# Current_sence-load-volt_meter.net
KiCad netlist of a schematic drawn in Altium Designer
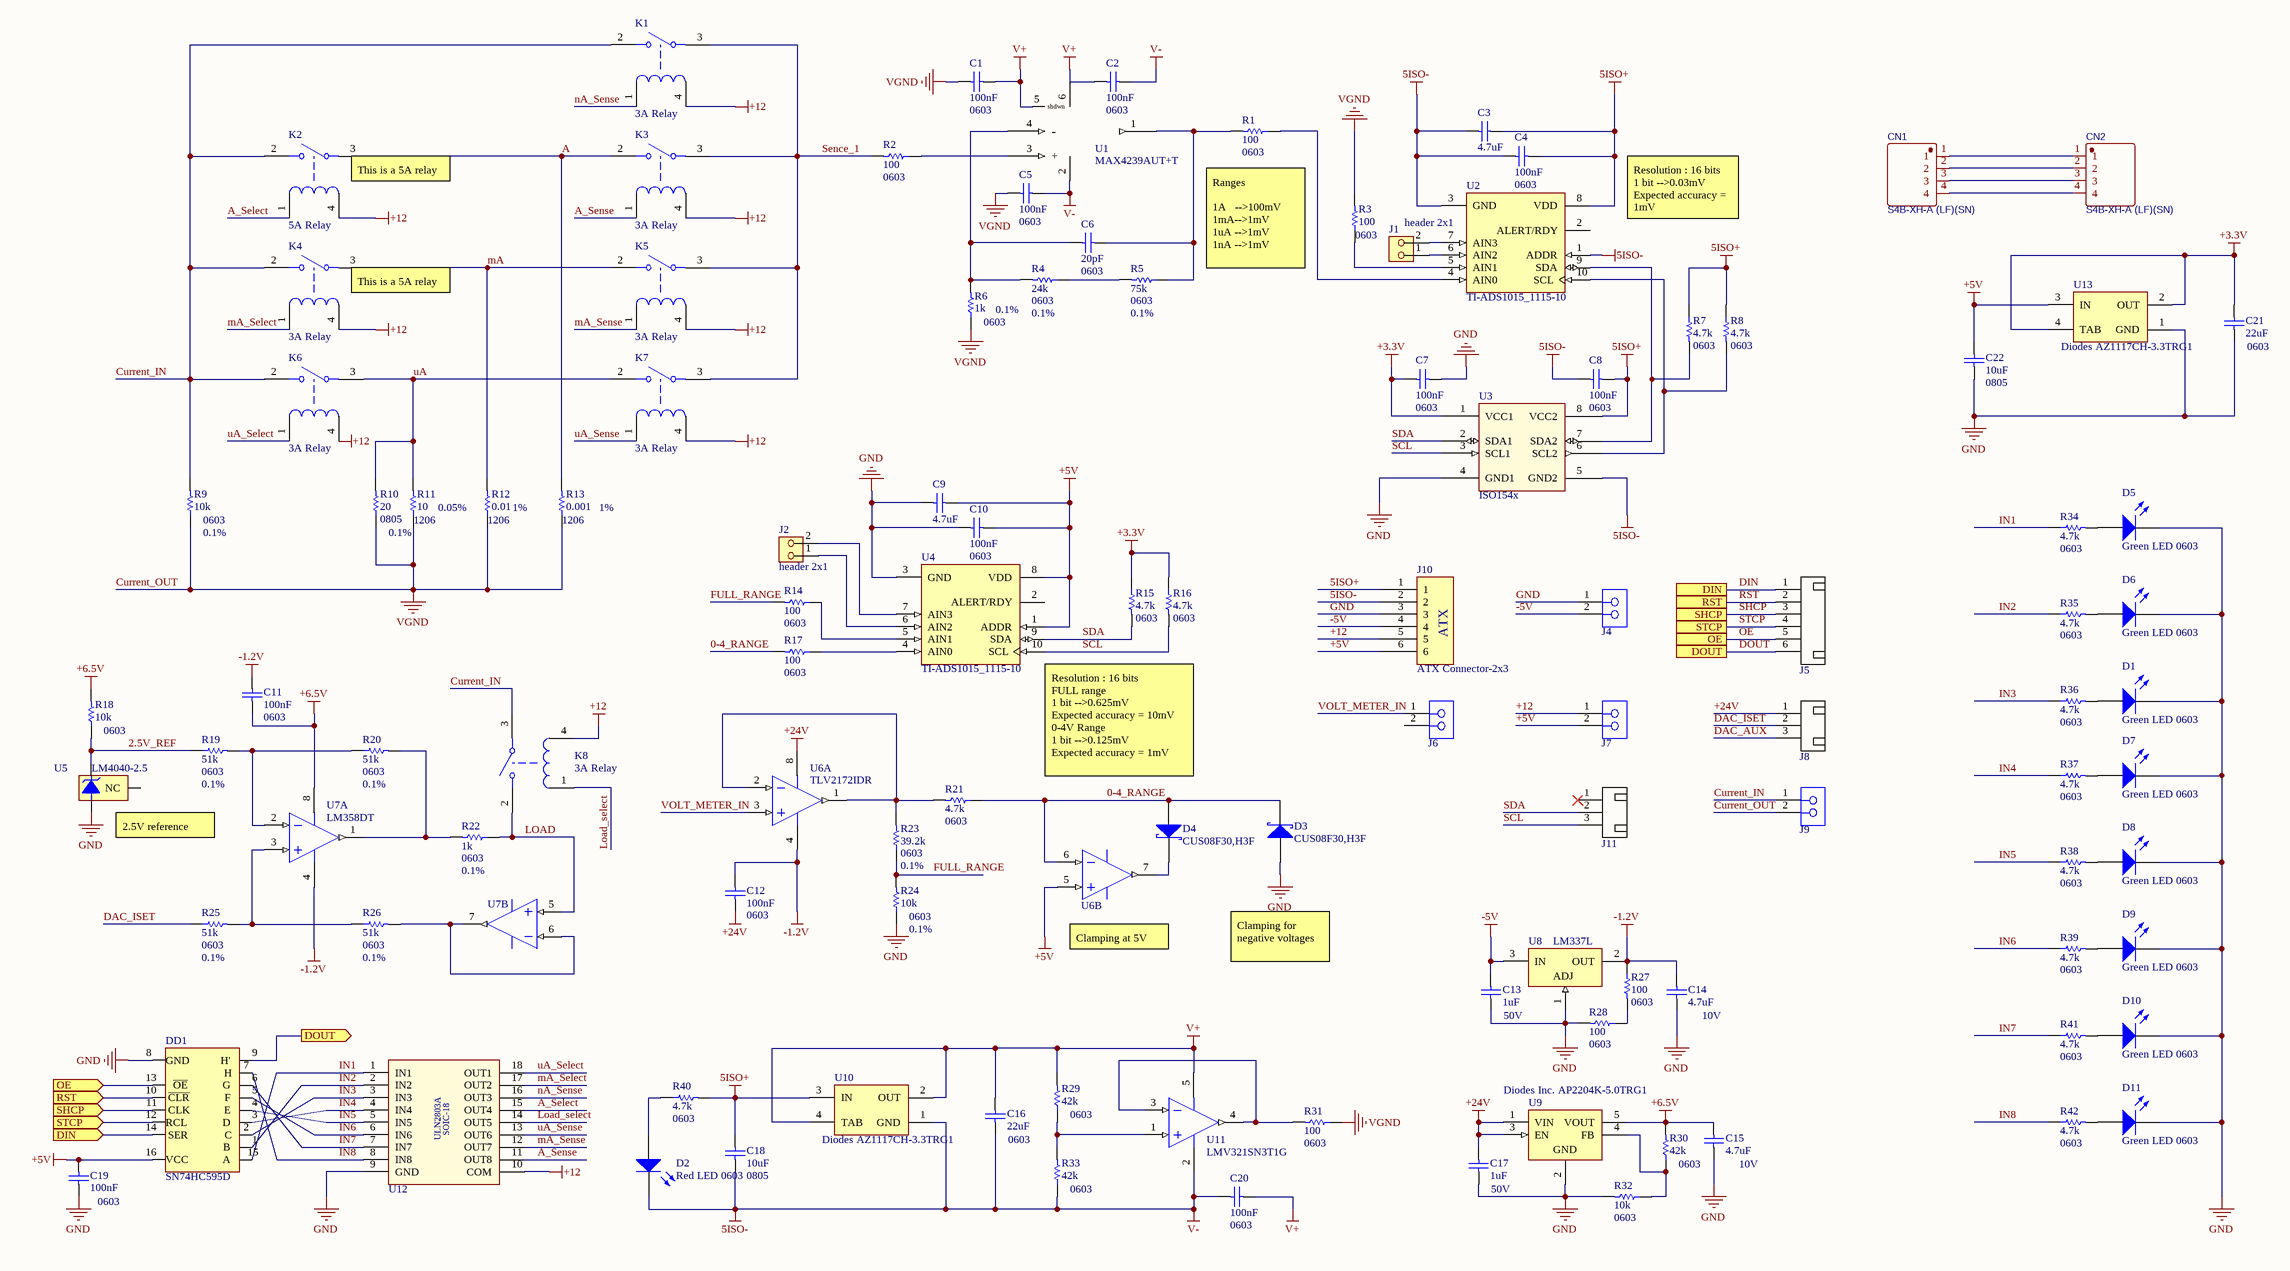
[diagram p0: Current_sence-load-volt_meter.SchDoc]

(export (version "E")
  (design (tool "Eeschema 10.0.6"))
  (components
    (comp (ref "C1")
      (value "100nF")
      (footprint "CAPC1608X09N")
      (description "0603 10 nF 50 V ± 10% Tolerance X7R Surface Mount Multilayer Ceramic Capacitor")
      (fields
        (field (name "MANUFACTURE PART NUMBER") "CC0603KRX7R9BB104")
        (field (name "MANUFACTURER") "YAGEO")
        (field (name "PACKAGE / CASE") "0603")
      )
      (libsource (lib "Current_sence_unit") (part "CMP-2f55e5122ad9f092-5"))
    )
    (comp (ref "C2")
      (value "100nF")
      (footprint "CAPC1608X09N")
      (description "0603 10 nF 50 V ± 10% Tolerance X7R Surface Mount Multilayer Ceramic Capacitor")
      (fields
        (field (name "MANUFACTURE PART NUMBER") "CC0603KRX7R9BB104")
        (field (name "MANUFACTURER") "YAGEO")
        (field (name "PACKAGE / CASE") "0603")
      )
      (libsource (lib "Current_sence_unit") (part "CMP-2f55e5122ad9f092-5"))
    )
    (comp (ref "C3")
      (value "4.7uF")
      (footprint "CAPC1608X09N")
      (description "0603 10 nF 50 V ± 10% Tolerance X7R Surface Mount Multilayer Ceramic Capacitor")
      (fields
        (field (name "MANUFACTURE PART NUMBER") "CL10A475KP8NNNC")
        (field (name "MANUFACTURER") "Samsung Electro-Mechanics")
      )
      (libsource (lib "Current_sence_unit") (part "CMP-2f55e5122ad9f092-5"))
    )
    (comp (ref "C4")
      (value "100nF")
      (footprint "CAPC1608X09N")
      (description "0603 10 nF 50 V ± 10% Tolerance X7R Surface Mount Multilayer Ceramic Capacitor")
      (fields
        (field (name "MANUFACTURE PART NUMBER") "CC0603KRX7R9BB104")
        (field (name "MANUFACTURER") "YAGEO")
        (field (name "PACKAGE / CASE") "0603")
      )
      (libsource (lib "Current_sence_unit") (part "CMP-2f55e5122ad9f092-5"))
    )
    (comp (ref "C5")
      (value "100nF")
      (footprint "CAPC1608X09N")
      (description "0603 10 nF 50 V ± 10% Tolerance X7R Surface Mount Multilayer Ceramic Capacitor")
      (fields
        (field (name "MANUFACTURE PART NUMBER") "CC0603KRX7R9BB104")
        (field (name "MANUFACTURER") "YAGEO")
        (field (name "PACKAGE / CASE") "0603")
      )
      (libsource (lib "Current_sence_unit") (part "CMP-2f55e5122ad9f092-5"))
    )
    (comp (ref "C6")
      (value "20pF")
      (footprint "CAPC1608X09N")
      (description "0603 10 nF 50 V ± 10% Tolerance X7R Surface Mount Multilayer Ceramic Capacitor")
      (fields
        (field (name "MANUFACTURE PART NUMBER") "CC0603JRNPO9BN200")
        (field (name "MANUFACTURER") "YAGEO")
        (field (name "PACKAGE / CASE") "0603")
      )
      (libsource (lib "Current_sence_unit") (part "CMP-2f55e5122ad9f092-5"))
    )
    (comp (ref "C7")
      (value "100nF")
      (footprint "CAPC1608X09N")
      (description "0603 10 nF 50 V ± 10% Tolerance X7R Surface Mount Multilayer Ceramic Capacitor")
      (fields
        (field (name "MANUFACTURE PART NUMBER") "CC0603KRX7R9BB104")
        (field (name "MANUFACTURER") "YAGEO")
        (field (name "PACKAGE / CASE") "0603")
      )
      (libsource (lib "Current_sence_unit") (part "CMP-2f55e5122ad9f092-5"))
    )
    (comp (ref "C8")
      (value "100nF")
      (footprint "CAPC1608X09N")
      (description "0603 10 nF 50 V ± 10% Tolerance X7R Surface Mount Multilayer Ceramic Capacitor")
      (fields
        (field (name "MANUFACTURE PART NUMBER") "CC0603KRX7R9BB104")
        (field (name "MANUFACTURER") "YAGEO")
        (field (name "PACKAGE / CASE") "0603")
      )
      (libsource (lib "Current_sence_unit") (part "CMP-2f55e5122ad9f092-5"))
    )
    (comp (ref "C9")
      (value "4.7uF")
      (footprint "CAPC1608X09N")
      (description "0603 10 nF 50 V ± 10% Tolerance X7R Surface Mount Multilayer Ceramic Capacitor")
      (fields
        (field (name "MANUFACTURE PART NUMBER") "CL10A475KP8NNNC")
        (field (name "MANUFACTURER") "Samsung Electro-Mechanics")
      )
      (libsource (lib "Current_sence_unit") (part "CMP-2f55e5122ad9f092-5"))
    )
    (comp (ref "C10")
      (value "100nF")
      (footprint "CAPC1608X09N")
      (description "0603 10 nF 50 V ± 10% Tolerance X7R Surface Mount Multilayer Ceramic Capacitor")
      (fields
        (field (name "MANUFACTURE PART NUMBER") "CC0603KRX7R9BB104")
        (field (name "MANUFACTURER") "YAGEO")
        (field (name "PACKAGE / CASE") "0603")
      )
      (libsource (lib "Current_sence_unit") (part "CMP-2f55e5122ad9f092-5"))
    )
    (comp (ref "C11")
      (value "100nF")
      (footprint "CAPC1608X09N")
      (description "0603 10 nF 50 V ± 10% Tolerance X7R Surface Mount Multilayer Ceramic Capacitor")
      (fields
        (field (name "MANUFACTURE PART NUMBER") "CC0603KRX7R9BB104")
        (field (name "MANUFACTURER") "YAGEO")
        (field (name "PACKAGE / CASE") "0603")
      )
      (libsource (lib "Current_sence_unit") (part "CMP-2f55e5122ad9f092-5"))
    )
    (comp (ref "C12")
      (value "100nF")
      (footprint "CAPC1608X09N")
      (description "0603 10 nF 50 V ± 10% Tolerance X7R Surface Mount Multilayer Ceramic Capacitor")
      (fields
        (field (name "MANUFACTURE PART NUMBER") "CC0603KRX7R9BB104")
        (field (name "MANUFACTURER") "YAGEO")
        (field (name "PACKAGE / CASE") "0603")
      )
      (libsource (lib "Current_sence_unit") (part "CMP-2f55e5122ad9f092-5"))
    )
    (comp (ref "C13")
      (value "1uF")
      (footprint "CAPC1608X09N")
      (description "0603 10 nF 50 V ± 10% Tolerance X7R Surface Mount Multilayer Ceramic Capacitor")
      (fields
        (field (name "VOLTAGE-RATED") "50V")
        (field (name "MANUFACTURE PART NUMBER") "CL21B105KBFNNNE")
        (field (name "MANUFACTURER") "Samsung Electro-Mechanics")
      )
      (libsource (lib "Current_sence_unit") (part "CMP-2f55e5122ad9f092-5"))
    )
    (comp (ref "C14")
      (value "4.7uF")
      (footprint "CAPC1608X09N")
      (description "0603 10 nF 50 V ± 10% Tolerance X7R Surface Mount Multilayer Ceramic Capacitor")
      (fields
        (field (name "VOLTAGE-RATED") "10V")
        (field (name "MANUFACTURE PART NUMBER") "CL10A475KP8NNNC")
        (field (name "MANUFACTURER") "Samsung Electro-Mechanics")
      )
      (libsource (lib "Current_sence_unit") (part "CMP-2f55e5122ad9f092-5"))
    )
    (comp (ref "C15")
      (value "4.7uF")
      (footprint "CAPC1608X09N")
      (description "0603 10 nF 50 V ± 10% Tolerance X7R Surface Mount Multilayer Ceramic Capacitor")
      (fields
        (field (name "VOLTAGE-RATED") "10V")
        (field (name "MANUFACTURE PART NUMBER") "CL10A475KP8NNNC")
        (field (name "MANUFACTURER") "Samsung Electro-Mechanics")
      )
      (libsource (lib "Current_sence_unit") (part "CMP-2f55e5122ad9f092-5"))
    )
    (comp (ref "C16")
      (value "22uF")
      (footprint "CAPC1608X09N")
      (description "0603 10 nF 50 V ± 10% Tolerance X7R Surface Mount Multilayer Ceramic Capacitor")
      (fields
        (field (name "MANUFACTURE PART NUMBER") "CL10A226MP8NUNE")
        (field (name "MANUFACTURER") "Samsung Electro-Mechanics")
        (field (name "PACKAGE / CASE") "0603")
      )
      (libsource (lib "Current_sence_unit") (part "CMP-2f55e5122ad9f092-5"))
    )
    (comp (ref "C17")
      (value "1uF")
      (footprint "CAPC1608X09N")
      (description "0603 10 nF 50 V ± 10% Tolerance X7R Surface Mount Multilayer Ceramic Capacitor")
      (fields
        (field (name "VOLTAGE-RATED") "50V")
        (field (name "MANUFACTURE PART NUMBER") "CL21B105KBFNNNE")
        (field (name "MANUFACTURER") "Samsung Electro-Mechanics")
      )
      (libsource (lib "Current_sence_unit") (part "CMP-2f55e5122ad9f092-5"))
    )
    (comp (ref "C18")
      (value "10uF")
      (footprint "C0805")
      (description "Cap Ceramic 0.1uF 50V X7R 10% SMD 0805 125C Embossed T/R")
      (fields
        (field (name "MANUFACTURE PART NUMBER") "CL21B106KOQNNNE")
        (field (name "PACKAGE / CASE") "0805")
        (field (name "MANUFACTURER") "Samsung Electro-Mechanics")
      )
      (libsource (lib "Current_sence_unit") (part "CMP-135114-3"))
    )
    (comp (ref "C19")
      (value "100nF")
      (footprint "CAPC1608X09N")
      (description "0603 10 nF 50 V ± 10% Tolerance X7R Surface Mount Multilayer Ceramic Capacitor")
      (fields
        (field (name "MANUFACTURE PART NUMBER") "CC0603KRX7R9BB104")
        (field (name "MANUFACTURER") "YAGEO")
        (field (name "PACKAGE / CASE") "0603")
      )
      (libsource (lib "Current_sence_unit") (part "CMP-2f55e5122ad9f092-5"))
    )
    (comp (ref "C20")
      (value "100nF")
      (footprint "CAPC1608X09N")
      (description "0603 10 nF 50 V ± 10% Tolerance X7R Surface Mount Multilayer Ceramic Capacitor")
      (fields
        (field (name "MANUFACTURE PART NUMBER") "CC0603KRX7R9BB104")
        (field (name "MANUFACTURER") "YAGEO")
        (field (name "PACKAGE / CASE") "0603")
      )
      (libsource (lib "Current_sence_unit") (part "CMP-2f55e5122ad9f092-5"))
    )
    (comp (ref "C21")
      (value "22uF")
      (footprint "CAPC1608X09N")
      (description "0603 10 nF 50 V ± 10% Tolerance X7R Surface Mount Multilayer Ceramic Capacitor")
      (fields
        (field (name "MANUFACTURE PART NUMBER") "CL10A226MP8NUNE")
        (field (name "MANUFACTURER") "Samsung Electro-Mechanics")
        (field (name "PACKAGE / CASE") "0603")
      )
      (libsource (lib "Current_sence_unit") (part "CMP-2f55e5122ad9f092-5"))
    )
    (comp (ref "C22")
      (value "10uF")
      (footprint "C0805")
      (description "Cap Ceramic 0.1uF 50V X7R 10% SMD 0805 125C Embossed T/R")
      (fields
        (field (name "MANUFACTURE PART NUMBER") "CL21B106KOQNNNE")
        (field (name "PACKAGE / CASE") "0805")
        (field (name "MANUFACTURER") "Samsung Electro-Mechanics")
      )
      (libsource (lib "Current_sence_unit") (part "CMP-135114-3"))
    )
    (comp (ref "CN1")
      (value "S4B-XH-A (LF)(SN)")
      (footprint "CONN-TH_S4B-XH-A (LF)(SN)")
      (fields (field (name "MANUFACTURER") "JST Sales America") (field (name "CONTRIBUTOR") "LCSC"))
      (libsource (lib "Main_MCU") (part "S4B-XH-A (LF)(SN)"))
    )
    (comp (ref "CN2")
      (value "S4B-XH-A (LF)(SN)")
      (footprint "CONN-TH_S4B-XH-A (LF)(SN)")
      (fields (field (name "MANUFACTURER") "JST Sales America") (field (name "CONTRIBUTOR") "LCSC"))
      (libsource (lib "Main_MCU") (part "S4B-XH-A (LF)(SN)"))
    )
    (comp (ref "D1")
      (value "Green LED 0603")
      (footprint "0603LED_GEN")
      (description "Generic LED 0603")
      (fields (field (name "MANUFACTURER") "Orient") (field (name "MANUFACTURE PART NUMBER") "ORH-G36G"))
      (libsource (lib "Current_sence_unit") (part "CMP-7ejgl1mi36gtz3spabtw-1"))
    )
    (comp (ref "D2")
      (value "Red LED 0603")
      (footprint "0603LED_GEN")
      (description "Generic LED 0603")
      (fields
        (field (name "MANUFACTURER") "Everlight Elec")
        (field (name "MANUFACTURE PART NUMBER") "19-217/R6C-AL1M2VY/3T")
      )
      (libsource (lib "Current_sence_unit") (part "CMP-7ejgl1mi36gtz3spabtw-1"))
    )
    (comp (ref "D3")
      (value "CUS08F30,H3F")
      (footprint "PCB-7qpkjsjx5cjbarp1o0hc-1")
      (description "Diode Schottky 30V 2-Pin SOD-323")
      (fields (field (name "MANUFACTURER") "TOSHIBA"))
      (libsource (lib "Current_sence_unit") (part "CMP-df191521a52000de-2"))
    )
    (comp (ref "D4")
      (value "CUS08F30,H3F")
      (footprint "PCB-7qpkjsjx5cjbarp1o0hc-1")
      (description "Diode Schottky 30V 2-Pin SOD-323")
      (fields (field (name "MANUFACTURER") "TOSHIBA"))
      (libsource (lib "Current_sence_unit") (part "CMP-df191521a52000de-2"))
    )
    (comp (ref "D5")
      (value "Green LED 0603")
      (footprint "0603LED_GEN")
      (description "Generic LED 0603")
      (fields (field (name "MANUFACTURER") "Orient") (field (name "MANUFACTURE PART NUMBER") "ORH-G36G"))
      (libsource (lib "Current_sence_unit") (part "CMP-7ejgl1mi36gtz3spabtw-1"))
    )
    (comp (ref "D6")
      (value "Green LED 0603")
      (footprint "0603LED_GEN")
      (description "Generic LED 0603")
      (fields (field (name "MANUFACTURER") "Orient") (field (name "MANUFACTURE PART NUMBER") "ORH-G36G"))
      (libsource (lib "Current_sence_unit") (part "CMP-7ejgl1mi36gtz3spabtw-1"))
    )
    (comp (ref "D7")
      (value "Green LED 0603")
      (footprint "0603LED_GEN")
      (description "Generic LED 0603")
      (fields (field (name "MANUFACTURER") "Orient") (field (name "MANUFACTURE PART NUMBER") "ORH-G36G"))
      (libsource (lib "Current_sence_unit") (part "CMP-7ejgl1mi36gtz3spabtw-1"))
    )
    (comp (ref "D8")
      (value "Green LED 0603")
      (footprint "0603LED_GEN")
      (description "Generic LED 0603")
      (fields (field (name "MANUFACTURER") "Orient") (field (name "MANUFACTURE PART NUMBER") "ORH-G36G"))
      (libsource (lib "Current_sence_unit") (part "CMP-7ejgl1mi36gtz3spabtw-1"))
    )
    (comp (ref "D9")
      (value "Green LED 0603")
      (footprint "0603LED_GEN")
      (description "Generic LED 0603")
      (fields (field (name "MANUFACTURER") "Orient") (field (name "MANUFACTURE PART NUMBER") "ORH-G36G"))
      (libsource (lib "Current_sence_unit") (part "CMP-7ejgl1mi36gtz3spabtw-1"))
    )
    (comp (ref "D10")
      (value "Green LED 0603")
      (footprint "0603LED_GEN")
      (description "Generic LED 0603")
      (fields (field (name "MANUFACTURER") "Orient") (field (name "MANUFACTURE PART NUMBER") "ORH-G36G"))
      (libsource (lib "Current_sence_unit") (part "CMP-7ejgl1mi36gtz3spabtw-1"))
    )
    (comp (ref "D11")
      (value "Green LED 0603")
      (footprint "0603LED_GEN")
      (description "Generic LED 0603")
      (fields (field (name "MANUFACTURER") "Orient") (field (name "MANUFACTURE PART NUMBER") "ORH-G36G"))
      (libsource (lib "Current_sence_unit") (part "CMP-7ejgl1mi36gtz3spabtw-1"))
    )
    (comp (ref "DD1")
      (value "SN74HC595D")
      (footprint "PCB-72k1vk0k27b6qyyenbg0-1")
      (description "Shift Register Single 8-Bit Serial to Serial/Parallel 16-Pin SOIC Tube")
      (fields
        (field (name "MANUFACTURE PART NUMBER") "74HC595D,118")
        (field (name "MANUFACTURER") "Nexperia")
      )
      (libsource (lib "Current_sence_unit") (part "CMP-ded317d957220114-5"))
    )
    (comp (ref "J1")
      (value "header 2x1")
      (footprint "PCB-55llon6gpk2h6a06nz0l-1")
      (description "2.54mm (.100\") Pitch C-Grid III Header, Single Row, Vertical, 1 Circuits, Gold (Au) Plating")
      (libsource (lib "Current_sence_unit") (part "SYM-8fae46aeaafe5069-1"))
    )
    (comp (ref "J2")
      (value "header 2x1")
      (footprint "PCB-55llon6gpk2h6a06nz0l-1")
      (description "2.54mm (.100\") Pitch C-Grid III Header, Single Row, Vertical, 1 Circuits, Gold (Au) Plating")
      (libsource (lib "Current_sence_unit") (part "SYM-8fae46aeaafe5069-1"))
    )
    (comp (ref "J4")
      (value "DB126V-5.0-2P-GN")
      (footprint "PCB-kiok1jlp9o9fcwf1wwvf-1")
      (description "Block, Terminal; 13.5 A; 250 V; 5 mm; 26 to 16 AWG; 2; Screw; Solder; 4 kV; PA")
      (fields (field (name "MANUFACTURER") "DIBO"))
      (libsource (lib "Current_sence_unit") (part "CMP-7ad9b3d37ed8a51e-5"))
    )
    (comp (ref "J5")
      (value "JST S6B-XH-A")
      (footprint "JST S6B-XH-A")
      (description "Socket; wire-board; male; PIN: 6; 2.5mm; THT; XH; 250V; 3A; -25÷85°C")
      (fields
        (field (name "MANUFACTURER") "JST Sales America")
        (field (name "MANUFACTURE PART NUMBER") "S6B-XH-A(LF)(SN)")
      )
      (libsource (lib "Current_sence_unit") (part "CMP-239aeae271c2fc5d-12"))
    )
    (comp (ref "J6")
      (value "DB126V-5.0-2P-GN")
      (footprint "PCB-kiok1jlp9o9fcwf1wwvf-1")
      (description "Block, Terminal; 13.5 A; 250 V; 5 mm; 26 to 16 AWG; 2; Screw; Solder; 4 kV; PA")
      (fields (field (name "MANUFACTURER") "DIBO"))
      (libsource (lib "Current_sence_unit") (part "CMP-7ad9b3d37ed8a51e-5"))
    )
    (comp (ref "J7")
      (value "DB126V-5.0-2P-GN")
      (footprint "PCB-kiok1jlp9o9fcwf1wwvf-1")
      (description "Block, Terminal; 13.5 A; 250 V; 5 mm; 26 to 16 AWG; 2; Screw; Solder; 4 kV; PA")
      (fields (field (name "MANUFACTURER") "DIBO"))
      (libsource (lib "Current_sence_unit") (part "CMP-7ad9b3d37ed8a51e-5"))
    )
    (comp (ref "J8")
      (value "CN-1P-M-R3")
      (footprint "JST-S3B-XH-A(LF)(SN)_V")
      (fields
        (field (name "MANUFACTURE PART NUMBER") "S3B-XH-A(LF)(SN)")
        (field (name "MANUFACTURER") "JST Sales America")
      )
      (libsource (lib "Current_sence_unit") (part "CMP-656568-19"))
    )
    (comp (ref "J9")
      (value "DB126V-5.0-2P-GN")
      (footprint "PCB-kiok1jlp9o9fcwf1wwvf-1")
      (description "Block, Terminal; 13.5 A; 250 V; 5 mm; 26 to 16 AWG; 2; Screw; Solder; 4 kV; PA")
      (fields (field (name "MANUFACTURER") "DIBO"))
      (libsource (lib "Current_sence_unit") (part "CMP-7ad9b3d37ed8a51e-5"))
    )
    (comp (ref "J10")
      (value "ATX Connector-2x3")
      (footprint "30300060")
      (description "Connector Header Through Hole, Right Angle 6 position 0.165\" (4.20mm)")
      (fields
        (field (name "MANUFACTURER") "BOOMELE(Boom Precision Elec)")
        (field (name "MANUFACTURE PART NUMBER") "5557-2*3AW")
      )
      (libsource (lib "Current_sence_unit") (part "39600060"))
    )
    (comp (ref "J11")
      (value "CN-1P-M-R3")
      (footprint "JST-S3B-XH-A(LF)(SN)_V")
      (fields
        (field (name "MANUFACTURE PART NUMBER") "S3B-XH-A(LF)(SN)")
        (field (name "MANUFACTURER") "JST Sales America")
      )
      (libsource (lib "Current_sence_unit") (part "CMP-656568-19"))
    )
    (comp (ref "K1")
      (value "3A Relay")
      (footprint "PCB-ei6nokn2irsc2a7yt94x-1")
      (description "Power Relay 12VDC 3DC/5AAC SPST-NO( (20.5mm 7.2mm 15.3mm)) THT")
      (fields
        (field (name "MANUFACTURER") "Omron Electronics")
        (field (name "MANUFACTURE PART NUMBER") "G5NB-1A-E-DC12")
      )
      (libsource (lib "Current_sence_unit") (part "CMP-edc624afa9603201-3"))
    )
    (comp (ref "K2")
      (value "5A Relay")
      (footprint "PCB-ei6nokn2irsc2a7yt94x-1")
      (description "General Purpose Non Latching 12VDC SPST-NO 5A Through Hole Relays RoHS")
      (fields
        (field (name "MANUFACTURER") "HF(Xiamen Hongfa Electroacoustic)")
        (field (name "MANUFACTURE PART NUMBER") "HF46F/12-HS1")
      )
      (libsource (lib "Current_sence_unit") (part "CMP-edc624afa9603201-3"))
    )
    (comp (ref "K3")
      (value "3A Relay")
      (footprint "PCB-ei6nokn2irsc2a7yt94x-1")
      (description "Power Relay 12VDC 3DC/5AAC SPST-NO( (20.5mm 7.2mm 15.3mm)) THT")
      (fields
        (field (name "MANUFACTURER") "Omron Electronics")
        (field (name "MANUFACTURE PART NUMBER") "G5NB-1A-E-DC12")
      )
      (libsource (lib "Current_sence_unit") (part "CMP-edc624afa9603201-3"))
    )
    (comp (ref "K4")
      (value "3A Relay")
      (footprint "PCB-ei6nokn2irsc2a7yt94x-1")
      (description "Power Relay 12VDC 3DC/5AAC SPST-NO( (20.5mm 7.2mm 15.3mm)) THT")
      (fields
        (field (name "MANUFACTURER") "Omron Electronics")
        (field (name "MANUFACTURE PART NUMBER") "G5NB-1A-E-DC12")
      )
      (libsource (lib "Current_sence_unit") (part "CMP-edc624afa9603201-3"))
    )
    (comp (ref "K5")
      (value "3A Relay")
      (footprint "PCB-ei6nokn2irsc2a7yt94x-1")
      (description "Power Relay 12VDC 3DC/5AAC SPST-NO( (20.5mm 7.2mm 15.3mm)) THT")
      (fields
        (field (name "MANUFACTURER") "Omron Electronics")
        (field (name "MANUFACTURE PART NUMBER") "G5NB-1A-E-DC12")
      )
      (libsource (lib "Current_sence_unit") (part "CMP-edc624afa9603201-3"))
    )
    (comp (ref "K6")
      (value "3A Relay")
      (footprint "PCB-ei6nokn2irsc2a7yt94x-1")
      (description "Power Relay 12VDC 3DC/5AAC SPST-NO( (20.5mm 7.2mm 15.3mm)) THT")
      (fields
        (field (name "MANUFACTURER") "Omron Electronics")
        (field (name "MANUFACTURE PART NUMBER") "G5NB-1A-E-DC12")
      )
      (libsource (lib "Current_sence_unit") (part "CMP-edc624afa9603201-3"))
    )
    (comp (ref "K7")
      (value "3A Relay")
      (footprint "PCB-ei6nokn2irsc2a7yt94x-1")
      (description "Power Relay 12VDC 3DC/5AAC SPST-NO( (20.5mm 7.2mm 15.3mm)) THT")
      (fields
        (field (name "MANUFACTURER") "Omron Electronics")
        (field (name "MANUFACTURE PART NUMBER") "G5NB-1A-E-DC12")
      )
      (libsource (lib "Current_sence_unit") (part "CMP-edc624afa9603201-3"))
    )
    (comp (ref "K8")
      (value "3A Relay")
      (footprint "PCB-ei6nokn2irsc2a7yt94x-1")
      (description "Power Relay 12VDC 3DC/5AAC SPST-NO( (20.5mm 7.2mm 15.3mm)) THT")
      (fields
        (field (name "MANUFACTURER") "Omron Electronics")
        (field (name "MANUFACTURE PART NUMBER") "G5NB-1A-E-DC12")
      )
      (libsource (lib "Current_sence_unit") (part "CMP-edc624afa9603201-3"))
    )
    (comp (ref "R1")
      (value "100")
      (footprint "gen0603-2")
      (description "Surface Mount Thick Film Resistor, RC Series, 1 kohm, 100 mW, - 1%, 50 V, 0603 [1608 Metric]")
      (fields
        (field (name "MANUFACTURE PART NUMBER") "0603WAF1000T5E")
        (field (name "MANUFACTURER") "UNI-ROYAL(Uniroyal Elec)")
        (field (name "PACKAGE / CASE") "0603")
      )
      (libsource (lib "Current_sence_unit") (part "CMP-1853278-27"))
    )
    (comp (ref "R2")
      (value "100")
      (footprint "gen0603-2")
      (description "Surface Mount Thick Film Resistor, RC Series, 1 kohm, 100 mW, - 1%, 50 V, 0603 [1608 Metric]")
      (fields
        (field (name "MANUFACTURE PART NUMBER") "0603WAF1000T5E")
        (field (name "MANUFACTURER") "UNI-ROYAL(Uniroyal Elec)")
        (field (name "PACKAGE / CASE") "0603")
      )
      (libsource (lib "Current_sence_unit") (part "CMP-1853278-27"))
    )
    (comp (ref "R3")
      (value "100")
      (footprint "gen0603-2")
      (description "Surface Mount Thick Film Resistor, RC Series, 1 kohm, 100 mW, - 1%, 50 V, 0603 [1608 Metric]")
      (fields
        (field (name "MANUFACTURE PART NUMBER") "0603WAF1000T5E")
        (field (name "MANUFACTURER") "UNI-ROYAL(Uniroyal Elec)")
        (field (name "PACKAGE / CASE") "0603")
      )
      (libsource (lib "Current_sence_unit") (part "CMP-1853278-27"))
    )
    (comp (ref "R4")
      (value "24k")
      (footprint "gen0603-2")
      (description "Surface Mount Thick Film Resistor, RC Series, 1 kohm, 100 mW, - 1%, 50 V, 0603 [1608 Metric]")
      (fields
        (field (name "MANUFACTURE PART NUMBER") "ERJPB3B2402V")
        (field (name "MANUFACTURER") "PANASONIC")
        (field (name "PACKAGE / CASE") "0603")
        (field (name "RESISTANCE TOLERANCE") "0.1%")
      )
      (libsource (lib "Current_sence_unit") (part "CMP-1853278-27"))
    )
    (comp (ref "R5")
      (value "75k")
      (footprint "gen0603-2")
      (description "Surface Mount Thick Film Resistor, RC Series, 1 kohm, 100 mW, - 1%, 50 V, 0603 [1608 Metric]")
      (fields
        (field (name "MANUFACTURE PART NUMBER") "ERJPB3B7502V")
        (field (name "MANUFACTURER") "PANASONIC")
        (field (name "PACKAGE / CASE") "0603")
        (field (name "RESISTANCE TOLERANCE") "0.1%")
      )
      (libsource (lib "Current_sence_unit") (part "CMP-1853278-27"))
    )
    (comp (ref "R6")
      (value "1k")
      (footprint "gen0603-2")
      (description "Surface Mount Thick Film Resistor, RC Series, 1 kohm, 100 mW, - 1%, 50 V, 0603 [1608 Metric]")
      (fields
        (field (name "MANUFACTURE PART NUMBER") "ERJPB3B1001V")
        (field (name "MANUFACTURER") "PANASONIC")
        (field (name "PACKAGE / CASE") "0603")
        (field (name "RESISTANCE TOLERANCE") "0.1%")
      )
      (libsource (lib "Current_sence_unit") (part "CMP-1853278-27"))
    )
    (comp (ref "R7")
      (value "4.7k")
      (footprint "gen0603-2")
      (description "Surface Mount Thick Film Resistor, RC Series, 1 kohm, 100 mW, - 1%, 50 V, 0603 [1608 Metric]")
      (fields
        (field (name "MANUFACTURE PART NUMBER") "RC0603FR-074K7L")
        (field (name "MANUFACTURER") "YAGEO")
        (field (name "PACKAGE / CASE") "0603")
      )
      (libsource (lib "Current_sence_unit") (part "CMP-1853278-27"))
    )
    (comp (ref "R8")
      (value "4.7k")
      (footprint "gen0603-2")
      (description "Surface Mount Thick Film Resistor, RC Series, 1 kohm, 100 mW, - 1%, 50 V, 0603 [1608 Metric]")
      (fields
        (field (name "MANUFACTURE PART NUMBER") "RC0603FR-074K7L")
        (field (name "MANUFACTURER") "YAGEO")
        (field (name "PACKAGE / CASE") "0603")
      )
      (libsource (lib "Current_sence_unit") (part "CMP-1853278-27"))
    )
    (comp (ref "R9")
      (value "10k")
      (footprint "gen0603-2")
      (description "Surface Mount Thick Film Resistor, RC Series, 1 kohm, 100 mW, - 1%, 50 V, 0603 [1608 Metric]")
      (fields
        (field (name "MANUFACTURE PART NUMBER") "WF06Q1002BTL")
        (field (name "MANUFACTURER") "Walsin Tech Corp")
        (field (name "PACKAGE / CASE") "0603")
        (field (name "RESISTANCE TOLERANCE") "0.1%")
      )
      (libsource (lib "Current_sence_unit") (part "CMP-1853278-27"))
    )
    (comp (ref "R10")
      (value "20")
      (footprint "PCB-p5gaxfzqzpvl2g018b4o-1")
      (description "Res Thin Film 0805 4.99 Ohm 0.1% 1/8W ±15ppm/°C Molded SMD SMD Paper T/R")
      (fields
        (field (name "MANUFACTURE PART NUMBER") "MCWF08U20R0BTL")
        (field (name "MANUFACTURER") "Multicomp")
        (field (name "PACKAGE / CASE") "0805")
        (field (name "RESISTANCE TOLERANCE") "0.1%")
      )
      (libsource (lib "Current_sence_unit") (part "CMP-f2923ac3d6042d55-1"))
    )
    (comp (ref "R11")
      (value "10")
      (footprint "RESC3116X07M")
      (description "Res Thick Film 3.2 x 1.6 mm 10K Ohm 1% 0.25W(1/4W) 100ppm/ C Molded SMD Paper T/R")
      (fields
        (field (name "MANUFACTURE PART NUMBER") "PE1206FKE470R01Z")
        (field (name "MANUFACTURER") "YAGEO")
        (field (name "PACKAGE / CASE") "1206")
        (field (name "RESISTANCE TOLERANCE") "0.05%")
      )
      (libsource (lib "Current_sence_unit") (part "CMP-90ca5a8d69034f0d-5"))
    )
    (comp (ref "R12")
      (value "0.01")
      (footprint "RESC3116X07M")
      (description "Res Thick Film 3.2 x 1.6 mm 10K Ohm 1% 0.25W(1/4W) 100ppm/ C Molded SMD Paper T/R")
      (fields
        (field (name "MANUFACTURE PART NUMBER") "PE1206FKE470R01Z")
        (field (name "MANUFACTURER") "YAGEO")
        (field (name "PACKAGE / CASE") "1206")
        (field (name "RESISTANCE TOLERANCE") "1%")
      )
      (libsource (lib "Current_sence_unit") (part "CMP-90ca5a8d69034f0d-5"))
    )
    (comp (ref "R13")
      (value "0.001")
      (footprint "RESC3116X07M")
      (description "Res Thick Film 3.2 x 1.6 mm 10K Ohm 1% 0.25W(1/4W) 100ppm/ C Molded SMD Paper T/R")
      (fields
        (field (name "MANUFACTURE PART NUMBER") "MA120610FR001SZ")
        (field (name "MANUFACTURER") "Ever Ohms Tech")
        (field (name "PACKAGE / CASE") "1206")
        (field (name "RESISTANCE TOLERANCE") "1%")
      )
      (libsource (lib "Current_sence_unit") (part "CMP-90ca5a8d69034f0d-5"))
    )
    (comp (ref "R14")
      (value "100")
      (footprint "gen0603-2")
      (description "Surface Mount Thick Film Resistor, RC Series, 1 kohm, 100 mW, - 1%, 50 V, 0603 [1608 Metric]")
      (fields
        (field (name "MANUFACTURE PART NUMBER") "0603WAF1000T5E")
        (field (name "MANUFACTURER") "UNI-ROYAL(Uniroyal Elec)")
        (field (name "PACKAGE / CASE") "0603")
      )
      (libsource (lib "Current_sence_unit") (part "CMP-1853278-27"))
    )
    (comp (ref "R15")
      (value "4.7k")
      (footprint "gen0603-2")
      (description "Surface Mount Thick Film Resistor, RC Series, 1 kohm, 100 mW, - 1%, 50 V, 0603 [1608 Metric]")
      (fields
        (field (name "MANUFACTURE PART NUMBER") "RC0603FR-074K7L")
        (field (name "MANUFACTURER") "YAGEO")
        (field (name "PACKAGE / CASE") "0603")
      )
      (libsource (lib "Current_sence_unit") (part "CMP-1853278-27"))
    )
    (comp (ref "R16")
      (value "4.7k")
      (footprint "gen0603-2")
      (description "Surface Mount Thick Film Resistor, RC Series, 1 kohm, 100 mW, - 1%, 50 V, 0603 [1608 Metric]")
      (fields
        (field (name "MANUFACTURE PART NUMBER") "RC0603FR-074K7L")
        (field (name "MANUFACTURER") "YAGEO")
        (field (name "PACKAGE / CASE") "0603")
      )
      (libsource (lib "Current_sence_unit") (part "CMP-1853278-27"))
    )
    (comp (ref "R17")
      (value "100")
      (footprint "gen0603-2")
      (description "Surface Mount Thick Film Resistor, RC Series, 1 kohm, 100 mW, - 1%, 50 V, 0603 [1608 Metric]")
      (fields
        (field (name "MANUFACTURE PART NUMBER") "0603WAF1000T5E")
        (field (name "MANUFACTURER") "UNI-ROYAL(Uniroyal Elec)")
        (field (name "PACKAGE / CASE") "0603")
      )
      (libsource (lib "Current_sence_unit") (part "CMP-1853278-27"))
    )
    (comp (ref "R18")
      (value "10k")
      (footprint "gen0603-2")
      (description "Surface Mount Thick Film Resistor, RC Series, 1 kohm, 100 mW, - 1%, 50 V, 0603 [1608 Metric]")
      (fields
        (field (name "MANUFACTURE PART NUMBER") "RC0603FR-0710KL")
        (field (name "MANUFACTURER") "YAGEO")
        (field (name "PACKAGE / CASE") "0603")
      )
      (libsource (lib "Current_sence_unit") (part "CMP-1853278-27"))
    )
    (comp (ref "R19")
      (value "51k")
      (footprint "gen0603-2")
      (description "Surface Mount Thick Film Resistor, RC Series, 1 kohm, 100 mW, - 1%, 50 V, 0603 [1608 Metric]")
      (fields
        (field (name "MANUFACTURE PART NUMBER") "ERJPB3B5102V")
        (field (name "MANUFACTURER") "PANASONIC")
        (field (name "PACKAGE / CASE") "0603")
        (field (name "RESISTANCE TOLERANCE") "0.1%")
      )
      (libsource (lib "Current_sence_unit") (part "CMP-1853278-27"))
    )
    (comp (ref "R20")
      (value "51k")
      (footprint "gen0603-2")
      (description "Surface Mount Thick Film Resistor, RC Series, 1 kohm, 100 mW, - 1%, 50 V, 0603 [1608 Metric]")
      (fields
        (field (name "MANUFACTURE PART NUMBER") "ERJPB3B5102V")
        (field (name "MANUFACTURER") "PANASONIC")
        (field (name "PACKAGE / CASE") "0603")
        (field (name "RESISTANCE TOLERANCE") "0.1%")
      )
      (libsource (lib "Current_sence_unit") (part "CMP-1853278-27"))
    )
    (comp (ref "R21")
      (value "4.7k")
      (footprint "gen0603-2")
      (description "Surface Mount Thick Film Resistor, RC Series, 1 kohm, 100 mW, - 1%, 50 V, 0603 [1608 Metric]")
      (fields
        (field (name "MANUFACTURE PART NUMBER") "RC0603FR-074K7L")
        (field (name "MANUFACTURER") "YAGEO")
        (field (name "PACKAGE / CASE") "0603")
      )
      (libsource (lib "Current_sence_unit") (part "CMP-1853278-27"))
    )
    (comp (ref "R22")
      (value "1k")
      (footprint "gen0603-2")
      (description "Surface Mount Thick Film Resistor, RC Series, 1 kohm, 100 mW, - 1%, 50 V, 0603 [1608 Metric]")
      (fields
        (field (name "MANUFACTURE PART NUMBER") "ERJPB3B1001V")
        (field (name "MANUFACTURER") "PANASONIC")
        (field (name "PACKAGE / CASE") "0603")
        (field (name "RESISTANCE TOLERANCE") "0.1%")
      )
      (libsource (lib "Current_sence_unit") (part "CMP-1853278-27"))
    )
    (comp (ref "R23")
      (value "39.2k")
      (footprint "gen0603-2")
      (description "Surface Mount Thick Film Resistor, RC Series, 1 kohm, 100 mW, - 1%, 50 V, 0603 [1608 Metric]")
      (fields
        (field (name "MANUFACTURE PART NUMBER") "ERA3AEB3922V")
        (field (name "MANUFACTURER") "PANASONIC")
        (field (name "PACKAGE / CASE") "0603")
        (field (name "RESISTANCE TOLERANCE") "0.1%")
      )
      (libsource (lib "Current_sence_unit") (part "CMP-1853278-27"))
    )
    (comp (ref "R24")
      (value "10k")
      (footprint "gen0603-2")
      (description "Surface Mount Thick Film Resistor, RC Series, 1 kohm, 100 mW, - 1%, 50 V, 0603 [1608 Metric]")
      (fields
        (field (name "MANUFACTURE PART NUMBER") "WF06Q1002BTL")
        (field (name "MANUFACTURER") "Walsin Tech Corp")
        (field (name "PACKAGE / CASE") "0603")
        (field (name "RESISTANCE TOLERANCE") "0.1%")
      )
      (libsource (lib "Current_sence_unit") (part "CMP-1853278-27"))
    )
    (comp (ref "R25")
      (value "51k")
      (footprint "gen0603-2")
      (description "Surface Mount Thick Film Resistor, RC Series, 1 kohm, 100 mW, - 1%, 50 V, 0603 [1608 Metric]")
      (fields
        (field (name "MANUFACTURE PART NUMBER") "ERJPB3B5102V")
        (field (name "MANUFACTURER") "PANASONIC")
        (field (name "PACKAGE / CASE") "0603")
        (field (name "RESISTANCE TOLERANCE") "0.1%")
      )
      (libsource (lib "Current_sence_unit") (part "CMP-1853278-27"))
    )
    (comp (ref "R26")
      (value "51k")
      (footprint "gen0603-2")
      (description "Surface Mount Thick Film Resistor, RC Series, 1 kohm, 100 mW, - 1%, 50 V, 0603 [1608 Metric]")
      (fields
        (field (name "MANUFACTURE PART NUMBER") "ERJPB3B5102V")
        (field (name "MANUFACTURER") "PANASONIC")
        (field (name "PACKAGE / CASE") "0603")
        (field (name "RESISTANCE TOLERANCE") "0.1%")
      )
      (libsource (lib "Current_sence_unit") (part "CMP-1853278-27"))
    )
    (comp (ref "R27")
      (value "100")
      (footprint "gen0603-2")
      (description "Surface Mount Thick Film Resistor, RC Series, 1 kohm, 100 mW, - 1%, 50 V, 0603 [1608 Metric]")
      (fields
        (field (name "MANUFACTURE PART NUMBER") "0603WAF1000T5E")
        (field (name "MANUFACTURER") "UNI-ROYAL(Uniroyal Elec)")
        (field (name "PACKAGE / CASE") "0603")
      )
      (libsource (lib "Current_sence_unit") (part "CMP-1853278-27"))
    )
    (comp (ref "R28")
      (value "100")
      (footprint "gen0603-2")
      (description "Surface Mount Thick Film Resistor, RC Series, 1 kohm, 100 mW, - 1%, 50 V, 0603 [1608 Metric]")
      (fields
        (field (name "MANUFACTURE PART NUMBER") "0603WAF1000T5E")
        (field (name "MANUFACTURER") "UNI-ROYAL(Uniroyal Elec)")
        (field (name "PACKAGE / CASE") "0603")
      )
      (libsource (lib "Current_sence_unit") (part "CMP-1853278-27"))
    )
    (comp (ref "R29")
      (value "42k")
      (footprint "gen0603-2")
      (description "Surface Mount Thick Film Resistor, RC Series, 1 kohm, 100 mW, - 1%, 50 V, 0603 [1608 Metric]")
      (fields
        (field (name "MANUFACTURE PART NUMBER") "0603WAF4222T5E")
        (field (name "MANUFACTURER") "UNI-ROYAL(Uniroyal Elec)")
        (field (name "PACKAGE / CASE") "0603")
      )
      (libsource (lib "Current_sence_unit") (part "CMP-1853278-27"))
    )
    (comp (ref "R30")
      (value "42k")
      (footprint "gen0603-2")
      (description "Surface Mount Thick Film Resistor, RC Series, 1 kohm, 100 mW, - 1%, 50 V, 0603 [1608 Metric]")
      (fields
        (field (name "MANUFACTURE PART NUMBER") "0603WAF4222T5E")
        (field (name "MANUFACTURER") "UNI-ROYAL(Uniroyal Elec)")
        (field (name "PACKAGE / CASE") "0603")
      )
      (libsource (lib "Current_sence_unit") (part "CMP-1853278-27"))
    )
    (comp (ref "R31")
      (value "100")
      (footprint "gen0603-2")
      (description "Surface Mount Thick Film Resistor, RC Series, 1 kohm, 100 mW, - 1%, 50 V, 0603 [1608 Metric]")
      (fields
        (field (name "MANUFACTURE PART NUMBER") "0603WAF1000T5E")
        (field (name "MANUFACTURER") "UNI-ROYAL(Uniroyal Elec)")
        (field (name "PACKAGE / CASE") "0603")
      )
      (libsource (lib "Current_sence_unit") (part "CMP-1853278-27"))
    )
    (comp (ref "R32")
      (value "10k")
      (footprint "gen0603-2")
      (description "Surface Mount Thick Film Resistor, RC Series, 1 kohm, 100 mW, - 1%, 50 V, 0603 [1608 Metric]")
      (fields
        (field (name "MANUFACTURE PART NUMBER") "RC0603FR-0710KL")
        (field (name "MANUFACTURER") "YAGEO")
        (field (name "PACKAGE / CASE") "0603")
      )
      (libsource (lib "Current_sence_unit") (part "CMP-1853278-27"))
    )
    (comp (ref "R33")
      (value "42k")
      (footprint "gen0603-2")
      (description "Surface Mount Thick Film Resistor, RC Series, 1 kohm, 100 mW, - 1%, 50 V, 0603 [1608 Metric]")
      (fields
        (field (name "MANUFACTURE PART NUMBER") "0603WAF4222T5E")
        (field (name "MANUFACTURER") "UNI-ROYAL(Uniroyal Elec)")
        (field (name "PACKAGE / CASE") "0603")
      )
      (libsource (lib "Current_sence_unit") (part "CMP-1853278-27"))
    )
    (comp (ref "R34")
      (value "4.7k")
      (footprint "gen0603-2")
      (description "Surface Mount Thick Film Resistor, RC Series, 1 kohm, 100 mW, - 1%, 50 V, 0603 [1608 Metric]")
      (fields
        (field (name "MANUFACTURE PART NUMBER") "RC0603FR-074K7L")
        (field (name "MANUFACTURER") "YAGEO")
        (field (name "PACKAGE / CASE") "0603")
      )
      (libsource (lib "Current_sence_unit") (part "CMP-1853278-27"))
    )
    (comp (ref "R35")
      (value "4.7k")
      (footprint "gen0603-2")
      (description "Surface Mount Thick Film Resistor, RC Series, 1 kohm, 100 mW, - 1%, 50 V, 0603 [1608 Metric]")
      (fields
        (field (name "MANUFACTURE PART NUMBER") "RC0603FR-074K7L")
        (field (name "MANUFACTURER") "YAGEO")
        (field (name "PACKAGE / CASE") "0603")
      )
      (libsource (lib "Current_sence_unit") (part "CMP-1853278-27"))
    )
    (comp (ref "R36")
      (value "4.7k")
      (footprint "gen0603-2")
      (description "Surface Mount Thick Film Resistor, RC Series, 1 kohm, 100 mW, - 1%, 50 V, 0603 [1608 Metric]")
      (fields
        (field (name "MANUFACTURE PART NUMBER") "RC0603FR-074K7L")
        (field (name "MANUFACTURER") "YAGEO")
        (field (name "PACKAGE / CASE") "0603")
      )
      (libsource (lib "Current_sence_unit") (part "CMP-1853278-27"))
    )
    (comp (ref "R37")
      (value "4.7k")
      (footprint "gen0603-2")
      (description "Surface Mount Thick Film Resistor, RC Series, 1 kohm, 100 mW, - 1%, 50 V, 0603 [1608 Metric]")
      (fields
        (field (name "MANUFACTURE PART NUMBER") "RC0603FR-074K7L")
        (field (name "MANUFACTURER") "YAGEO")
        (field (name "PACKAGE / CASE") "0603")
      )
      (libsource (lib "Current_sence_unit") (part "CMP-1853278-27"))
    )
    (comp (ref "R38")
      (value "4.7k")
      (footprint "gen0603-2")
      (description "Surface Mount Thick Film Resistor, RC Series, 1 kohm, 100 mW, - 1%, 50 V, 0603 [1608 Metric]")
      (fields
        (field (name "MANUFACTURE PART NUMBER") "RC0603FR-074K7L")
        (field (name "MANUFACTURER") "YAGEO")
        (field (name "PACKAGE / CASE") "0603")
      )
      (libsource (lib "Current_sence_unit") (part "CMP-1853278-27"))
    )
    (comp (ref "R39")
      (value "4.7k")
      (footprint "gen0603-2")
      (description "Surface Mount Thick Film Resistor, RC Series, 1 kohm, 100 mW, - 1%, 50 V, 0603 [1608 Metric]")
      (fields
        (field (name "MANUFACTURE PART NUMBER") "RC0603FR-074K7L")
        (field (name "MANUFACTURER") "YAGEO")
        (field (name "PACKAGE / CASE") "0603")
      )
      (libsource (lib "Current_sence_unit") (part "CMP-1853278-27"))
    )
    (comp (ref "R40")
      (value "4.7k")
      (footprint "gen0603-2")
      (description "Surface Mount Thick Film Resistor, RC Series, 1 kohm, 100 mW, - 1%, 50 V, 0603 [1608 Metric]")
      (fields
        (field (name "MANUFACTURE PART NUMBER") "RC0603FR-074K7L")
        (field (name "MANUFACTURER") "YAGEO")
        (field (name "PACKAGE / CASE") "0603")
      )
      (libsource (lib "Current_sence_unit") (part "CMP-1853278-27"))
    )
    (comp (ref "R41")
      (value "4.7k")
      (footprint "gen0603-2")
      (description "Surface Mount Thick Film Resistor, RC Series, 1 kohm, 100 mW, - 1%, 50 V, 0603 [1608 Metric]")
      (fields
        (field (name "MANUFACTURE PART NUMBER") "RC0603FR-074K7L")
        (field (name "MANUFACTURER") "YAGEO")
        (field (name "PACKAGE / CASE") "0603")
      )
      (libsource (lib "Current_sence_unit") (part "CMP-1853278-27"))
    )
    (comp (ref "R42")
      (value "4.7k")
      (footprint "gen0603-2")
      (description "Surface Mount Thick Film Resistor, RC Series, 1 kohm, 100 mW, - 1%, 50 V, 0603 [1608 Metric]")
      (fields
        (field (name "MANUFACTURE PART NUMBER") "RC0603FR-074K7L")
        (field (name "MANUFACTURER") "YAGEO")
        (field (name "PACKAGE / CASE") "0603")
      )
      (libsource (lib "Current_sence_unit") (part "CMP-1853278-27"))
    )
    (comp (ref "U1")
      (value "MAX4239AUT+T")
      (footprint "MF06A_N")
      (description "OP Amp Single GP R-R O/P 5.5V 6-Pin SOT-23 T/R")
      (fields (field (name "MANUFACTURER") "Maxim Integrated"))
      (libsource (lib "Current_sence_unit") (part "CMP-250bee9e4f44facc-2"))
    )
    (comp (ref "U2")
      (value "TI-ADS1015_1115-10")
      (footprint "PCB-gqbslbs1r8rxldsn6t09-1")
      (description "Quad Channel Single ADC Delta-Sigma 860sps 16-bit Serial 10-Pin VSSOP T/R")
      (fields
        (field (name "MANUFACTURER") "Texas Instruments")
        (field (name "MANUFACTURE PART NUMBER") "ADS1115IDGST")
      )
      (libsource (lib "Current_sence_unit") (part "CMP-19361522-7"))
    )
    (comp (ref "U3")
      (value "ISO154x")
      (footprint "SOIC127P600X265-8N")
      (description "Low-Power, Bidirectional I2C Isolators 8-SOIC -40 to 125")
      (fields
        (field (name "MANUFACTURE PART NUMBER") "ISO1541DR")
        (field (name "MANUFACTURER") "Texas Instruments")
      )
      (libsource (lib "Current_sence_unit") (part "CMP-4359179-9"))
    )
    (comp (ref "U4")
      (value "TI-ADS1015_1115-10")
      (footprint "PCB-gqbslbs1r8rxldsn6t09-1")
      (description "Quad Channel Single ADC Delta-Sigma 860sps 16-bit Serial 10-Pin VSSOP T/R")
      (fields
        (field (name "MANUFACTURER") "Texas Instruments")
        (field (name "MANUFACTURE PART NUMBER") "ADS1115IDGST")
      )
      (libsource (lib "Current_sence_unit") (part "CMP-19361522-7"))
    )
    (comp (ref "U5")
      (value "LM4040-2.5")
      (footprint "MF03A_N")
      (description "Precision Micropower Shunt Voltage Reference, 3-pin SOT-23, Pb-Free")
      (fields
        (field (name "MANUFACTURE PART NUMBER") "LM4040D25FTA")
        (field (name "MANUFACTURER") "Diodes Incorporated")
      )
      (libsource (lib "Current_sence_unit") (part "LM4040CEM3-2.5/NOPB"))
    )
    (comp (ref "U6")
      (value "CMP-9a3c516d515145fb-3")
      (footprint "SOIC-OA8_M")
      (fields
        (field (name "MANUFACTURE PART NUMBER") "TLV2172IDR")
        (field (name "MANUFACTURER") "Texas Instruments")
      )
      (libsource (lib "Current_sence_unit") (part "CMP-9a3c516d515145fb-3"))
    )
    (comp (ref "U7")
      (value "LM358DT")
      (footprint "SOIC-OA8_M")
      (description "LM358 Series 30 V 1.1 MHz Low Power Dual Operational Amplifier - SOIC-8")
      (fields
        (field (name "MANUFACTURE PART NUMBER") "LM358DT")
        (field (name "MANUFACTURER") "STMicroelectronics")
      )
      (libsource (lib "Current_sence_unit") (part "CMP-9a3c516d515145fb-3"))
    )
    (comp (ref "U8")
      (value "LM337L")
      (footprint "Z03A")
      (description "3-Terminal Adjustable Regulator, 3-pin TO-92, Pb-Free")
      (fields
        (field (name "MANUFACTURE PART NUMBER") "LM337LZ/NOPB")
        (field (name "MANUFACTURER") "Texas Instruments")
      )
      (libsource (lib "Current_sence_unit") (part "LM337LZ/NOPB"))
    )
    (comp (ref "U9")
      (value "Diodes Inc. AP2204K-5.0TRG1")
      (footprint "PCB-iw3p7s72x6qbi5zew47f-1")
      (description "LDO voltage regulator [Diodes Incorporated] AP2204K-5.0TRG1 LDO voltage regulator")
      (fields
        (field (name "MANUFACTURE PART NUMBER") "AP2204K-ADJTRG1")
        (field (name "MANUFACTURER") "Diodes Incorporated")
      )
      (libsource (lib "Current_sence_unit") (part "CMP-6ce4a4361dffb323-1"))
    )
    (comp (ref "U10")
      (value "Diodes AZ1117CH-3.3TRG1")
      (footprint "PCB-15095235-1")
      (description "IC REG LDO 3.3V 0.8A SOT223")
      (fields
        (field (name "MANUFACTURE PART NUMBER") "AZ1117CH-3.3TRG1")
        (field (name "MANUFACTURER") "Diodes Incorporated")
      )
      (libsource (lib "Current_sence_unit") (part "CMP-15095235-4"))
    )
    (comp (ref "U11")
      (value "LMV321SN3T1G")
      (footprint "ONSC-TSOP-5-483-02_V")
      (fields (field (name "MANUFACTURER") "Gainsil") (field (name "MANUFACTURE PART NUMBER") "LMV321-TR"))
      (libsource (lib "Current_sence_unit") (part "CMP-1330714-2"))
    )
    (comp (ref "U12")
      (value "ULN2803A (SOIC-18)")
      (footprint "PCB-gcdku7p92m9mz9ih2yin-1")
      (description "Bipolar (BJT) Array Transistor, Darlington, NPN, 50 V, 500 mA, SOIC")
      (fields (field (name "MANUFACTURE PART NUMBER") "ULN2803A") (field (name "MANUFACTURER") "Mixic"))
      (libsource (lib "Current_sence_unit") (part "CMP-19353911-22"))
    )
    (comp (ref "U13")
      (value "Diodes AZ1117CH-3.3TRG1")
      (footprint "PCB-15095235-1")
      (description "IC REG LDO 3.3V 0.8A SOT223")
      (fields
        (field (name "MANUFACTURE PART NUMBER") "AZ1117CH-3.3TRG1")
        (field (name "MANUFACTURER") "Diodes Incorporated")
      )
      (libsource (lib "Current_sence_unit") (part "CMP-15095235-4"))
    )
  )
  (nets
    (net (code "1") (name "+3.3V") (class "Default")
      (node (ref "C21") (pin "2") (pinfunction "2_2") (pintype "passive"))
      (node (ref "C7") (pin "2") (pinfunction "2_2") (pintype "passive"))
      (node (ref "R15") (pin "1") (pinfunction "1_1") (pintype "passive"))
      (node (ref "R16") (pin "1") (pinfunction "1_1") (pintype "passive"))
      (node (ref "U13") (pin "2") (pinfunction "OUT_2") (pintype "power_in"))
      (node (ref "U13") (pin "4") (pinfunction "TAB_4") (pintype "power_in"))
      (node (ref "U3") (pin "1") (pinfunction "VCC1_1") (pintype "power_in"))
    )
    (net (code "2") (name "+5V") (class "Default")
      (node (ref "C10") (pin "1") (pinfunction "1_1") (pintype "passive"))
      (node (ref "C19") (pin "2") (pinfunction "2_2") (pintype "passive"))
      (node (ref "C22") (pin "2") (pinfunction "2_2") (pintype "passive"))
      (node (ref "C9") (pin "1") (pinfunction "1_1") (pintype "passive"))
      (node (ref "DD1") (pin "16") (pinfunction "VCC_16") (pintype "passive"))
      (node (ref "J10") (pin "6") (pinfunction "6_6") (pintype "passive"))
      (node (ref "J7") (pin "2") (pinfunction "2_2") (pintype "passive"))
      (node (ref "U13") (pin "3") (pinfunction "IN_3") (pintype "power_in"))
      (node (ref "U4") (pin "1") (pinfunction "ADDR_1") (pintype "input"))
      (node (ref "U4") (pin "8") (pinfunction "VDD_8") (pintype "power_in"))
      (node (ref "U6") (pin "5") (pinfunction "INB+_5") (pintype "input"))
    )
    (net (code "3") (name "+6.5V") (class "Default")
      (node (ref "C11") (pin "2") (pinfunction "2_2") (pintype "passive"))
      (node (ref "C15") (pin "2") (pinfunction "2_2") (pintype "passive"))
      (node (ref "R18") (pin "2") (pinfunction "2_2") (pintype "passive"))
      (node (ref "R30") (pin "2") (pinfunction "2_2") (pintype "passive"))
      (node (ref "U7") (pin "8") (pinfunction "VCC_8") (pintype "power_in"))
      (node (ref "U9") (pin "5") (pinfunction "VOUT_5") (pintype "power_in"))
    )
    (net (code "4") (name "+12") (class "Default")
      (node (ref "J10") (pin "5") (pinfunction "5_5") (pintype "passive"))
      (node (ref "J7") (pin "1") (pinfunction "1_1") (pintype "passive"))
      (node (ref "K1") (pin "4") (pinfunction "4_4") (pintype "passive"))
      (node (ref "K2") (pin "4") (pinfunction "4_4") (pintype "passive"))
      (node (ref "K3") (pin "4") (pinfunction "4_4") (pintype "passive"))
      (node (ref "K4") (pin "4") (pinfunction "4_4") (pintype "passive"))
      (node (ref "K5") (pin "4") (pinfunction "4_4") (pintype "passive"))
      (node (ref "K6") (pin "4") (pinfunction "4_4") (pintype "passive"))
      (node (ref "K7") (pin "4") (pinfunction "4_4") (pintype "passive"))
      (node (ref "K8") (pin "4") (pinfunction "4_4") (pintype "passive"))
      (node (ref "U12") (pin "10") (pinfunction "COM_10") (pintype "power_in"))
    )
    (net (code "5") (name "+24V") (class "Default")
      (node (ref "C12") (pin "2") (pinfunction "2_2") (pintype "passive"))
      (node (ref "C17") (pin "2") (pinfunction "2_2") (pintype "passive"))
      (node (ref "J8") (pin "1") (pinfunction "1_1") (pintype "passive"))
      (node (ref "U6") (pin "8") (pinfunction "VCC_8") (pintype "power_in"))
      (node (ref "U9") (pin "1") (pinfunction "VIN_1") (pintype "power_in"))
      (node (ref "U9") (pin "3") (pinfunction "EN_3") (pintype "input"))
    )
    (net (code "6") (name "-1.2V") (class "Default")
      (node (ref "C11") (pin "1") (pinfunction "1_1") (pintype "passive"))
      (node (ref "C12") (pin "1") (pinfunction "1_1") (pintype "passive"))
      (node (ref "C14") (pin "2") (pinfunction "2_2") (pintype "passive"))
      (node (ref "R27") (pin "1") (pinfunction "1_1") (pintype "passive"))
      (node (ref "U6") (pin "4") (pinfunction "VEE/GND_4") (pintype "power_in"))
      (node (ref "U7") (pin "4") (pinfunction "VEE/GND_4") (pintype "power_in"))
      (node (ref "U8") (pin "2") (pinfunction "OUT_2") (pintype "power_in"))
    )
    (net (code "7") (name "-5V") (class "Default")
      (node (ref "C13") (pin "2") (pinfunction "2_2") (pintype "passive"))
      (node (ref "J10") (pin "4") (pinfunction "4_4") (pintype "passive"))
      (node (ref "J4") (pin "2") (pinfunction "2_2") (pintype "passive"))
      (node (ref "U8") (pin "3") (pinfunction "IN_3") (pintype "power_in"))
    )
    (net (code "8") (name "/0-4_RANGE") (class "Default")
      (node (ref "D3") (pin "1") (pinfunction "K_1") (pintype "passive"))
      (node (ref "D4") (pin "2") (pinfunction "A_2") (pintype "passive"))
      (node (ref "R17") (pin "2") (pinfunction "2_2") (pintype "passive"))
      (node (ref "R21") (pin "1") (pinfunction "1_1") (pintype "passive"))
      (node (ref "U6") (pin "6") (pinfunction "INB-_6") (pintype "input"))
    )
    (net (code "9") (name "/2.5V_REF") (class "Default")
      (node (ref "R18") (pin "1") (pinfunction "1_1") (pintype "passive"))
      (node (ref "R19") (pin "1") (pinfunction "1_1") (pintype "passive"))
      (node (ref "U5") (pin "1") (pinfunction "+V_1") (pintype "passive"))
    )
    (net (code "10") (name "/A") (class "Default")
      (node (ref "K2") (pin "3") (pinfunction "3_3") (pintype "passive"))
      (node (ref "K3") (pin "2") (pinfunction "2_2") (pintype "passive"))
      (node (ref "R13") (pin "2") (pinfunction "2_2") (pintype "passive"))
    )
    (net (code "11") (name "/A_Select") (class "Default")
      (node (ref "K2") (pin "1") (pinfunction "1_1") (pintype "passive"))
      (node (ref "U12") (pin "15") (pinfunction "OUT4_15") (pintype "power_in"))
    )
    (net (code "12") (name "/A_Sense") (class "Default")
      (node (ref "K3") (pin "1") (pinfunction "1_1") (pintype "passive"))
      (node (ref "U12") (pin "11") (pinfunction "OUT8_11") (pintype "power_in"))
    )
    (net (code "13") (name "/Current_IN") (class "Default")
      (node (ref "J9") (pin "1") (pinfunction "1_1") (pintype "passive"))
      (node (ref "K1") (pin "2") (pinfunction "2_2") (pintype "passive"))
      (node (ref "K2") (pin "2") (pinfunction "2_2") (pintype "passive"))
      (node (ref "K4") (pin "2") (pinfunction "2_2") (pintype "passive"))
      (node (ref "K6") (pin "2") (pinfunction "2_2") (pintype "passive"))
      (node (ref "K8") (pin "3") (pinfunction "3_3") (pintype "passive"))
      (node (ref "R9") (pin "2") (pinfunction "2_2") (pintype "passive"))
    )
    (net (code "14") (name "/DAC_AUX") (class "Default")
      (node (ref "J8") (pin "3") (pinfunction "3_3") (pintype "passive"))
    )
    (net (code "15") (name "/DAC_ISET") (class "Default")
      (node (ref "J8") (pin "2") (pinfunction "2_2") (pintype "passive"))
      (node (ref "R25") (pin "1") (pinfunction "1_1") (pintype "passive"))
    )
    (net (code "16") (name "/DIN") (class "Default")
      (node (ref "DD1") (pin "14") (pinfunction "SER_14") (pintype "passive"))
      (node (ref "J5") (pin "1") (pinfunction "1_1") (pintype "passive"))
    )
    (net (code "17") (name "/DOUT") (class "Default")
      (node (ref "DD1") (pin "9") (pinfunction "H'_9") (pintype "passive"))
      (node (ref "J5") (pin "6") (pinfunction "6_6") (pintype "passive"))
    )
    (net (code "18") (name "/FULL_RANGE") (class "Default")
      (node (ref "R14") (pin "2") (pinfunction "2_2") (pintype "passive"))
      (node (ref "R23") (pin "1") (pinfunction "1_1") (pintype "passive"))
      (node (ref "R24") (pin "2") (pinfunction "2_2") (pintype "passive"))
    )
    (net (code "19") (name "/IN1") (class "Default")
      (node (ref "DD1") (pin "15") (pinfunction "A_15") (pintype "passive"))
      (node (ref "R34") (pin "1") (pinfunction "1_1") (pintype "passive"))
      (node (ref "U12") (pin "1") (pinfunction "IN1_1") (pintype "passive"))
    )
    (net (code "20") (name "/IN2") (class "Default")
      (node (ref "DD1") (pin "1") (pinfunction "B_1") (pintype "passive"))
      (node (ref "R35") (pin "1") (pinfunction "1_1") (pintype "passive"))
      (node (ref "U12") (pin "2") (pinfunction "IN2_2") (pintype "passive"))
    )
    (net (code "21") (name "/IN3") (class "Default")
      (node (ref "DD1") (pin "2") (pinfunction "C_2") (pintype "passive"))
      (node (ref "R36") (pin "1") (pinfunction "1_1") (pintype "passive"))
      (node (ref "U12") (pin "3") (pinfunction "IN3_3") (pintype "passive"))
    )
    (net (code "22") (name "/IN4") (class "Default")
      (node (ref "DD1") (pin "3") (pinfunction "D_3") (pintype "passive"))
      (node (ref "R37") (pin "1") (pinfunction "1_1") (pintype "passive"))
      (node (ref "U12") (pin "4") (pinfunction "IN4_4") (pintype "passive"))
    )
    (net (code "23") (name "/IN5") (class "Default")
      (node (ref "DD1") (pin "4") (pinfunction "E_4") (pintype "passive"))
      (node (ref "R38") (pin "1") (pinfunction "1_1") (pintype "passive"))
      (node (ref "U12") (pin "5") (pinfunction "IN5_5") (pintype "passive"))
    )
    (net (code "24") (name "/IN6") (class "Default")
      (node (ref "DD1") (pin "5") (pinfunction "F_5") (pintype "passive"))
      (node (ref "R39") (pin "1") (pinfunction "1_1") (pintype "passive"))
      (node (ref "U12") (pin "6") (pinfunction "IN6_6") (pintype "passive"))
    )
    (net (code "25") (name "/IN7") (class "Default")
      (node (ref "DD1") (pin "6") (pinfunction "G_6") (pintype "passive"))
      (node (ref "R41") (pin "1") (pinfunction "1_1") (pintype "passive"))
      (node (ref "U12") (pin "7") (pinfunction "IN7_7") (pintype "passive"))
    )
    (net (code "26") (name "/IN8") (class "Default")
      (node (ref "DD1") (pin "7") (pinfunction "H_7") (pintype "passive"))
      (node (ref "R42") (pin "1") (pinfunction "1_1") (pintype "passive"))
      (node (ref "U12") (pin "8") (pinfunction "IN8_8") (pintype "passive"))
    )
    (net (code "27") (name "/LOAD") (class "Default")
      (node (ref "K8") (pin "2") (pinfunction "2_2") (pintype "passive"))
      (node (ref "R22") (pin "1") (pinfunction "1_1") (pintype "passive"))
      (node (ref "U7") (pin "5") (pinfunction "INB+_5") (pintype "input"))
    )
    (net (code "28") (name "/Load_select") (class "Default")
      (node (ref "K8") (pin "1") (pinfunction "1_1") (pintype "passive"))
      (node (ref "U12") (pin "14") (pinfunction "OUT5_14") (pintype "power_in"))
    )
    (net (code "29") (name "/OE") (class "Default")
      (node (ref "DD1") (pin "13") (pinfunction "~{OE}_13") (pintype "passive"))
      (node (ref "J5") (pin "5") (pinfunction "5_5") (pintype "passive"))
    )
    (net (code "30") (name "/RST") (class "Default")
      (node (ref "DD1") (pin "10") (pinfunction "~{CLR}_10") (pintype "passive"))
      (node (ref "J5") (pin "2") (pinfunction "2_2") (pintype "passive"))
    )
    (net (code "31") (name "/SCL") (class "Default")
      (node (ref "J11") (pin "3") (pinfunction "3_3") (pintype "passive"))
      (node (ref "R16") (pin "2") (pinfunction "2_2") (pintype "passive"))
      (node (ref "U3") (pin "3") (pinfunction "SCL1_3") (pintype "input"))
      (node (ref "U4") (pin "10") (pinfunction "SCL_10") (pintype "input"))
    )
    (net (code "32") (name "/SDA") (class "Default")
      (node (ref "J11") (pin "2") (pinfunction "2_2") (pintype "passive"))
      (node (ref "R15") (pin "2") (pinfunction "2_2") (pintype "passive"))
      (node (ref "U3") (pin "2") (pinfunction "SDA1_2") (pintype "bidirectional"))
      (node (ref "U4") (pin "9") (pinfunction "SDA_9") (pintype "bidirectional"))
    )
    (net (code "33") (name "/SHCP") (class "Default")
      (node (ref "DD1") (pin "11") (pinfunction "CLK_11") (pintype "passive"))
      (node (ref "J5") (pin "3") (pinfunction "3_3") (pintype "passive"))
    )
    (net (code "34") (name "/STCP") (class "Default")
      (node (ref "DD1") (pin "12") (pinfunction "RCL_12") (pintype "passive"))
      (node (ref "J5") (pin "4") (pinfunction "4_4") (pintype "passive"))
    )
    (net (code "35") (name "/Sence_1") (class "Default")
      (node (ref "K1") (pin "3") (pinfunction "3_3") (pintype "passive"))
      (node (ref "K3") (pin "3") (pinfunction "3_3") (pintype "passive"))
      (node (ref "K5") (pin "3") (pinfunction "3_3") (pintype "passive"))
      (node (ref "K7") (pin "3") (pinfunction "3_3") (pintype "passive"))
      (node (ref "R2") (pin "2") (pinfunction "2_2") (pintype "passive"))
    )
    (net (code "36") (name "/VOLT_METER_IN") (class "Default")
      (node (ref "J6") (pin "1") (pinfunction "1_1") (pintype "passive"))
      (node (ref "U6") (pin "3") (pinfunction "INA+_3") (pintype "input"))
    )
    (net (code "37") (name "/mA") (class "Default")
      (node (ref "K4") (pin "3") (pinfunction "3_3") (pintype "passive"))
      (node (ref "K5") (pin "2") (pinfunction "2_2") (pintype "passive"))
      (node (ref "R12") (pin "2") (pinfunction "2_2") (pintype "passive"))
    )
    (net (code "38") (name "/mA_Select") (class "Default")
      (node (ref "K4") (pin "1") (pinfunction "1_1") (pintype "passive"))
      (node (ref "U12") (pin "17") (pinfunction "OUT2_17") (pintype "power_in"))
    )
    (net (code "39") (name "/mA_Sense") (class "Default")
      (node (ref "K5") (pin "1") (pinfunction "1_1") (pintype "passive"))
      (node (ref "U12") (pin "12") (pinfunction "OUT7_12") (pintype "power_in"))
    )
    (net (code "40") (name "/nA_Sense") (class "Default")
      (node (ref "K1") (pin "1") (pinfunction "1_1") (pintype "passive"))
      (node (ref "U12") (pin "16") (pinfunction "OUT3_16") (pintype "power_in"))
    )
    (net (code "41") (name "/uA") (class "Default")
      (node (ref "K6") (pin "3") (pinfunction "3_3") (pintype "passive"))
      (node (ref "K7") (pin "2") (pinfunction "2_2") (pintype "passive"))
      (node (ref "R10") (pin "2") (pinfunction "2_2") (pintype "passive"))
      (node (ref "R11") (pin "2") (pinfunction "2_2") (pintype "passive"))
    )
    (net (code "42") (name "/uA_Select") (class "Default")
      (node (ref "K6") (pin "1") (pinfunction "1_1") (pintype "passive"))
      (node (ref "U12") (pin "18") (pinfunction "OUT1_18") (pintype "power_in"))
    )
    (net (code "43") (name "/uA_Sense") (class "Default")
      (node (ref "K7") (pin "1") (pinfunction "1_1") (pintype "passive"))
      (node (ref "U12") (pin "13") (pinfunction "OUT6_13") (pintype "power_in"))
    )
    (net (code "44") (name "5ISO+") (class "Default")
      (node (ref "C18") (pin "2") (pinfunction "2_2") (pintype "passive"))
      (node (ref "C3") (pin "1") (pinfunction "1_1") (pintype "passive"))
      (node (ref "C4") (pin "1") (pinfunction "1_1") (pintype "passive"))
      (node (ref "C8") (pin "2") (pinfunction "2_2") (pintype "passive"))
      (node (ref "J10") (pin "1") (pinfunction "1_1") (pintype "passive"))
      (node (ref "R40") (pin "2") (pinfunction "2_2") (pintype "passive"))
      (node (ref "R7") (pin "1") (pinfunction "1_1") (pintype "passive"))
      (node (ref "R8") (pin "1") (pinfunction "1_1") (pintype "passive"))
      (node (ref "U10") (pin "3") (pinfunction "IN_3") (pintype "power_in"))
      (node (ref "U2") (pin "8") (pinfunction "VDD_8") (pintype "power_in"))
      (node (ref "U3") (pin "8") (pinfunction "VCC2_8") (pintype "power_in"))
    )
    (net (code "45") (name "5ISO-") (class "Default")
      (node (ref "C16") (pin "1") (pinfunction "1_1") (pintype "passive"))
      (node (ref "C18") (pin "1") (pinfunction "1_1") (pintype "passive"))
      (node (ref "C2") (pin "1") (pinfunction "1_1") (pintype "passive"))
      (node (ref "C20") (pin "2") (pinfunction "2_2") (pintype "passive"))
      (node (ref "C3") (pin "2") (pinfunction "2_2") (pintype "passive"))
      (node (ref "C4") (pin "2") (pinfunction "2_2") (pintype "passive"))
      (node (ref "C5") (pin "1") (pinfunction "1_1") (pintype "passive"))
      (node (ref "C8") (pin "1") (pinfunction "1_1") (pintype "passive"))
      (node (ref "D2") (pin "2") (pinfunction "K_2") (pintype "passive"))
      (node (ref "J10") (pin "2") (pinfunction "2_2") (pintype "passive"))
      (node (ref "R33") (pin "1") (pinfunction "1_1") (pintype "passive"))
      (node (ref "U1") (pin "2") (pinfunction "V-_2") (pintype "power_in"))
      (node (ref "U10") (pin "1") (pinfunction "GND_1") (pintype "power_in"))
      (node (ref "U11") (pin "2") (pinfunction "V-_2") (pintype "power_in"))
      (node (ref "U2") (pin "1") (pinfunction "ADDR_1") (pintype "input"))
      (node (ref "U2") (pin "3") (pinfunction "GND_3") (pintype "power_in"))
      (node (ref "U3") (pin "5") (pinfunction "GND2_5") (pintype "power_in"))
    )
    (net (code "46") (name "GND") (class "Default")
      (node (ref "C10") (pin "2") (pinfunction "2_2") (pintype "passive"))
      (node (ref "C13") (pin "1") (pinfunction "1_1") (pintype "passive"))
      (node (ref "C14") (pin "1") (pinfunction "1_1") (pintype "passive"))
      (node (ref "C15") (pin "1") (pinfunction "1_1") (pintype "passive"))
      (node (ref "C17") (pin "1") (pinfunction "1_1") (pintype "passive"))
      (node (ref "C19") (pin "1") (pinfunction "1_1") (pintype "passive"))
      (node (ref "C21") (pin "1") (pinfunction "1_1") (pintype "passive"))
      (node (ref "C22") (pin "1") (pinfunction "1_1") (pintype "passive"))
      (node (ref "C7") (pin "1") (pinfunction "1_1") (pintype "passive"))
      (node (ref "C9") (pin "2") (pinfunction "2_2") (pintype "passive"))
      (node (ref "D1") (pin "2") (pinfunction "K_2") (pintype "passive"))
      (node (ref "D10") (pin "2") (pinfunction "K_2") (pintype "passive"))
      (node (ref "D11") (pin "2") (pinfunction "K_2") (pintype "passive"))
      (node (ref "D3") (pin "2") (pinfunction "A_2") (pintype "passive"))
      (node (ref "D5") (pin "2") (pinfunction "K_2") (pintype "passive"))
      (node (ref "D6") (pin "2") (pinfunction "K_2") (pintype "passive"))
      (node (ref "D7") (pin "2") (pinfunction "K_2") (pintype "passive"))
      (node (ref "D8") (pin "2") (pinfunction "K_2") (pintype "passive"))
      (node (ref "D9") (pin "2") (pinfunction "K_2") (pintype "passive"))
      (node (ref "DD1") (pin "8") (pinfunction "GND_8") (pintype "passive"))
      (node (ref "J10") (pin "3") (pinfunction "3_3") (pintype "passive"))
      (node (ref "J4") (pin "1") (pinfunction "1_1") (pintype "passive"))
      (node (ref "R24") (pin "1") (pinfunction "1_1") (pintype "passive"))
      (node (ref "R28") (pin "2") (pinfunction "2_2") (pintype "passive"))
      (node (ref "R32") (pin "2") (pinfunction "2_2") (pintype "passive"))
      (node (ref "U12") (pin "9") (pinfunction "GND_9") (pintype "power_in"))
      (node (ref "U13") (pin "1") (pinfunction "GND_1") (pintype "power_in"))
      (node (ref "U3") (pin "4") (pinfunction "GND1_4") (pintype "power_in"))
      (node (ref "U4") (pin "3") (pinfunction "GND_3") (pintype "power_in"))
      (node (ref "U5") (pin "2") (pinfunction "-V_2") (pintype "passive"))
      (node (ref "U8") (pin "1") (pinfunction "ADJ_1") (pintype "input"))
      (node (ref "U9") (pin "2") (pinfunction "GND_2") (pintype "power_in"))
    )
    (net (code "47") (name "Net-(C6-Pad1)") (class "Default")
      (node (ref "C6") (pin "1") (pinfunction "1_1") (pintype "passive"))
      (node (ref "R1") (pin "2") (pinfunction "2_2") (pintype "passive"))
      (node (ref "R5") (pin "1") (pinfunction "1_1") (pintype "passive"))
      (node (ref "U1") (pin "1") (pintype "output"))
    )
    (net (code "48") (name "Net-(CN1-Pad1)") (class "Default")
      (node (ref "CN1") (pin "1") (pinfunction "1_1") (pintype "passive"))
      (node (ref "CN2") (pin "1") (pinfunction "1_1") (pintype "passive"))
    )
    (net (code "49") (name "Net-(CN1-Pad2)") (class "Default")
      (node (ref "CN1") (pin "2") (pinfunction "2_2") (pintype "passive"))
      (node (ref "CN2") (pin "2") (pinfunction "2_2") (pintype "passive"))
    )
    (net (code "50") (name "Net-(CN1-Pad3)") (class "Default")
      (node (ref "CN1") (pin "3") (pinfunction "3_3") (pintype "passive"))
      (node (ref "CN2") (pin "3") (pinfunction "3_3") (pintype "passive"))
    )
    (net (code "51") (name "Net-(CN1-Pad4)") (class "Default")
      (node (ref "CN1") (pin "4") (pinfunction "4_4") (pintype "passive"))
      (node (ref "CN2") (pin "4") (pinfunction "4_4") (pintype "passive"))
    )
    (net (code "52") (name "Net-(D1-A)") (class "Default")
      (node (ref "D1") (pin "1") (pinfunction "A_1") (pintype "passive"))
      (node (ref "R36") (pin "2") (pinfunction "2_2") (pintype "passive"))
    )
    (net (code "53") (name "Net-(D2-A)") (class "Default")
      (node (ref "D2") (pin "1") (pinfunction "A_1") (pintype "passive"))
      (node (ref "R40") (pin "1") (pinfunction "1_1") (pintype "passive"))
    )
    (net (code "54") (name "Net-(D4-K)") (class "Default")
      (node (ref "D4") (pin "1") (pinfunction "K_1") (pintype "passive"))
      (node (ref "U6") (pin "7") (pinfunction "OUTB_7") (pintype "output"))
    )
    (net (code "55") (name "Net-(D5-A)") (class "Default")
      (node (ref "D5") (pin "1") (pinfunction "A_1") (pintype "passive"))
      (node (ref "R34") (pin "2") (pinfunction "2_2") (pintype "passive"))
    )
    (net (code "56") (name "Net-(D6-A)") (class "Default")
      (node (ref "D6") (pin "1") (pinfunction "A_1") (pintype "passive"))
      (node (ref "R35") (pin "2") (pinfunction "2_2") (pintype "passive"))
    )
    (net (code "57") (name "Net-(D7-A)") (class "Default")
      (node (ref "D7") (pin "1") (pinfunction "A_1") (pintype "passive"))
      (node (ref "R37") (pin "2") (pinfunction "2_2") (pintype "passive"))
    )
    (net (code "58") (name "Net-(D8-A)") (class "Default")
      (node (ref "D8") (pin "1") (pinfunction "A_1") (pintype "passive"))
      (node (ref "R38") (pin "2") (pinfunction "2_2") (pintype "passive"))
    )
    (net (code "59") (name "Net-(D9-A)") (class "Default")
      (node (ref "D9") (pin "1") (pinfunction "A_1") (pintype "passive"))
      (node (ref "R39") (pin "2") (pinfunction "2_2") (pintype "passive"))
    )
    (net (code "60") (name "Net-(D10-A)") (class "Default")
      (node (ref "D10") (pin "1") (pinfunction "A_1") (pintype "passive"))
      (node (ref "R41") (pin "2") (pinfunction "2_2") (pintype "passive"))
    )
    (net (code "61") (name "Net-(D11-A)") (class "Default")
      (node (ref "D11") (pin "1") (pinfunction "A_1") (pintype "passive"))
      (node (ref "R42") (pin "2") (pinfunction "2_2") (pintype "passive"))
    )
    (net (code "62") (name "Net-(R4-Pad1)") (class "Default")
      (node (ref "R4") (pin "1") (pinfunction "1_1") (pintype "passive"))
      (node (ref "R5") (pin "2") (pinfunction "2_2") (pintype "passive"))
    )
    (net (code "63") (name "Net-(R27-Pad2)") (class "Default")
      (node (ref "R27") (pin "2") (pinfunction "2_2") (pintype "passive"))
      (node (ref "R28") (pin "1") (pinfunction "1_1") (pintype "passive"))
    )
    (net (code "64") (name "Net-(U1-+)") (class "Default")
      (node (ref "R2") (pin "1") (pinfunction "1_1") (pintype "passive"))
      (node (ref "U1") (pin "3") (pinfunction "+_3") (pintype "input"))
    )
    (net (code "65") (name "Net-(U1--)") (class "Default")
      (node (ref "C6") (pin "2") (pinfunction "2_2") (pintype "passive"))
      (node (ref "R4") (pin "2") (pinfunction "2_2") (pintype "passive"))
      (node (ref "R6") (pin "2") (pinfunction "2_2") (pintype "passive"))
      (node (ref "U1") (pin "4") (pinfunction "-_4") (pintype "input"))
    )
    (net (code "66") (name "Net-(U2-AIN0)") (class "Default")
      (node (ref "R1") (pin "1") (pinfunction "1_1") (pintype "passive"))
      (node (ref "U2") (pin "4") (pinfunction "AIN0_4") (pintype "input"))
    )
    (net (code "67") (name "Net-(U2-AIN1)") (class "Default")
      (node (ref "R3") (pin "1") (pinfunction "1_1") (pintype "passive"))
      (node (ref "U2") (pin "5") (pinfunction "AIN1_5") (pintype "input"))
    )
    (net (code "68") (name "Net-(U2-AIN2)") (class "Default")
      (node (ref "J1") (pin "1") (pinfunction "1_1") (pintype "passive"))
      (node (ref "U2") (pin "6") (pinfunction "AIN2_6") (pintype "input"))
    )
    (net (code "69") (name "Net-(U2-AIN3)") (class "Default")
      (node (ref "J1") (pin "2") (pinfunction "2_2") (pintype "passive"))
      (node (ref "U2") (pin "7") (pinfunction "AIN3_7") (pintype "input"))
    )
    (net (code "70") (name "Net-(U2-SCL)") (class "Default")
      (node (ref "R8") (pin "2") (pinfunction "2_2") (pintype "passive"))
      (node (ref "U2") (pin "10") (pinfunction "SCL_10") (pintype "input"))
      (node (ref "U3") (pin "6") (pinfunction "SCL2_6") (pintype "output"))
    )
    (net (code "71") (name "Net-(U2-SDA)") (class "Default")
      (node (ref "R7") (pin "2") (pinfunction "2_2") (pintype "passive"))
      (node (ref "U2") (pin "9") (pinfunction "SDA_9") (pintype "bidirectional"))
      (node (ref "U3") (pin "7") (pinfunction "SDA2_7") (pintype "bidirectional"))
    )
    (net (code "72") (name "Net-(U4-AIN0)") (class "Default")
      (node (ref "R17") (pin "1") (pinfunction "1_1") (pintype "passive"))
      (node (ref "U4") (pin "4") (pinfunction "AIN0_4") (pintype "input"))
    )
    (net (code "73") (name "Net-(U4-AIN1)") (class "Default")
      (node (ref "R14") (pin "1") (pinfunction "1_1") (pintype "passive"))
      (node (ref "U4") (pin "5") (pinfunction "AIN1_5") (pintype "input"))
    )
    (net (code "74") (name "Net-(U4-AIN2)") (class "Default")
      (node (ref "J2") (pin "1") (pinfunction "1_1") (pintype "passive"))
      (node (ref "U4") (pin "6") (pinfunction "AIN2_6") (pintype "input"))
    )
    (net (code "75") (name "Net-(U4-AIN3)") (class "Default")
      (node (ref "J2") (pin "2") (pinfunction "2_2") (pintype "passive"))
      (node (ref "U4") (pin "7") (pinfunction "AIN3_7") (pintype "input"))
    )
    (net (code "76") (name "Net-(U6A-INA-)") (class "Default")
      (node (ref "R21") (pin "2") (pinfunction "2_2") (pintype "passive"))
      (node (ref "R23") (pin "2") (pinfunction "2_2") (pintype "passive"))
      (node (ref "U6") (pin "1") (pinfunction "OUTA_1") (pintype "output"))
      (node (ref "U6") (pin "2") (pinfunction "INA-_2") (pintype "input"))
    )
    (net (code "77") (name "Net-(U7A-INA+)") (class "Default")
      (node (ref "R25") (pin "2") (pinfunction "2_2") (pintype "passive"))
      (node (ref "R26") (pin "1") (pinfunction "1_1") (pintype "passive"))
      (node (ref "U7") (pin "3") (pinfunction "INA+_3") (pintype "input"))
    )
    (net (code "78") (name "Net-(U7A-INA-)") (class "Default")
      (node (ref "R19") (pin "2") (pinfunction "2_2") (pintype "passive"))
      (node (ref "R20") (pin "1") (pinfunction "1_1") (pintype "passive"))
      (node (ref "U7") (pin "2") (pinfunction "INA-_2") (pintype "input"))
    )
    (net (code "79") (name "Net-(U7A-OUTA)") (class "Default")
      (node (ref "R20") (pin "2") (pinfunction "2_2") (pintype "passive"))
      (node (ref "R22") (pin "2") (pinfunction "2_2") (pintype "passive"))
      (node (ref "U7") (pin "1") (pinfunction "OUTA_1") (pintype "output"))
    )
    (net (code "80") (name "Net-(U7B-INB-)") (class "Default")
      (node (ref "R26") (pin "2") (pinfunction "2_2") (pintype "passive"))
      (node (ref "U7") (pin "6") (pinfunction "INB-_6") (pintype "input"))
      (node (ref "U7") (pin "7") (pinfunction "OUTB_7") (pintype "output"))
    )
    (net (code "81") (name "Net-(U9-FB)") (class "Default")
      (node (ref "R30") (pin "1") (pinfunction "1_1") (pintype "passive"))
      (node (ref "R32") (pin "1") (pinfunction "1_1") (pintype "passive"))
      (node (ref "U9") (pin "4") (pinfunction "FB_4") (pintype "passive"))
    )
    (net (code "82") (name "Net-(U11-IN+)") (class "Default")
      (node (ref "R29") (pin "1") (pinfunction "1_1") (pintype "passive"))
      (node (ref "R33") (pin "2") (pinfunction "2_2") (pintype "passive"))
      (node (ref "U11") (pin "1") (pinfunction "IN+_1") (pintype "input"))
    )
    (net (code "83") (name "Net-(U11-IN-)") (class "Default")
      (node (ref "R31") (pin "2") (pinfunction "2_2") (pintype "passive"))
      (node (ref "U11") (pin "3") (pinfunction "IN-_3") (pintype "input"))
      (node (ref "U11") (pin "4") (pinfunction "OUT_4") (pintype "output"))
    )
    (net (code "84") (name "V+") (class "Default")
      (node (ref "C1") (pin "1") (pinfunction "1_1") (pintype "passive"))
      (node (ref "C16") (pin "2") (pinfunction "2_2") (pintype "passive"))
      (node (ref "C2") (pin "2") (pinfunction "2_2") (pintype "passive"))
      (node (ref "C20") (pin "1") (pinfunction "1_1") (pintype "passive"))
      (node (ref "R29") (pin "2") (pinfunction "2_2") (pintype "passive"))
      (node (ref "U1") (pin "5") (pinfunction "shdwn_5") (pintype "passive"))
      (node (ref "U10") (pin "2") (pinfunction "OUT_2") (pintype "power_in"))
      (node (ref "U10") (pin "4") (pinfunction "TAB_4") (pintype "power_in"))
      (node (ref "U11") (pin "5") (pinfunction "V+_5") (pintype "power_in"))
    )
    (net (code "85") (name "VGND") (class "Default")
      (node (ref "C1") (pin "2") (pinfunction "2_2") (pintype "passive"))
      (node (ref "C5") (pin "2") (pinfunction "2_2") (pintype "passive"))
      (node (ref "J9") (pin "2") (pinfunction "2_2") (pintype "passive"))
      (node (ref "R10") (pin "1") (pinfunction "1_1") (pintype "passive"))
      (node (ref "R11") (pin "1") (pinfunction "1_1") (pintype "passive"))
      (node (ref "R12") (pin "1") (pinfunction "1_1") (pintype "passive"))
      (node (ref "R13") (pin "1") (pinfunction "1_1") (pintype "passive"))
      (node (ref "R3") (pin "2") (pinfunction "2_2") (pintype "passive"))
      (node (ref "R31") (pin "1") (pinfunction "1_1") (pintype "passive"))
      (node (ref "R6") (pin "1") (pinfunction "1_1") (pintype "passive"))
      (node (ref "R9") (pin "1") (pinfunction "1_1") (pintype "passive"))
    )
    (net (code "86") (name "unconnected-(J6-Pad2)") (class "Default")
      (node (ref "J6") (pin "2") (pinfunction "2_2") (pintype "passive"))
    )
    (net (code "87") (name "unconnected-(J11-Pad1)") (class "Default")
      (node (ref "J11") (pin "1") (pinfunction "1_1") (pintype "passive+no_connect"))
    )
    (net (code "88") (name "unconnected-(U1-V+-Pad6)") (class "Default")
      (node (ref "U1") (pin "6") (pinfunction "V+_6") (pintype "power_in"))
    )
    (net (code "89") (name "unconnected-(U2-ALERT{slash}RDY-Pad2)") (class "Default")
      (node (ref "U2") (pin "2") (pinfunction "ALERT/RDY_2") (pintype "open_collector"))
    )
    (net (code "90") (name "unconnected-(U4-ALERT{slash}RDY-Pad2)") (class "Default")
      (node (ref "U4") (pin "2") (pinfunction "ALERT/RDY_2") (pintype "open_collector"))
    )
    (net (code "91") (name "unconnected-(U5-NC-Pad3)") (class "Default")
      (node (ref "U5") (pin "3") (pinfunction "NC_3") (pintype "passive"))
    )
  )
)
